# yaw.net
KiCad netlist of a schematic drawn in EAGLE
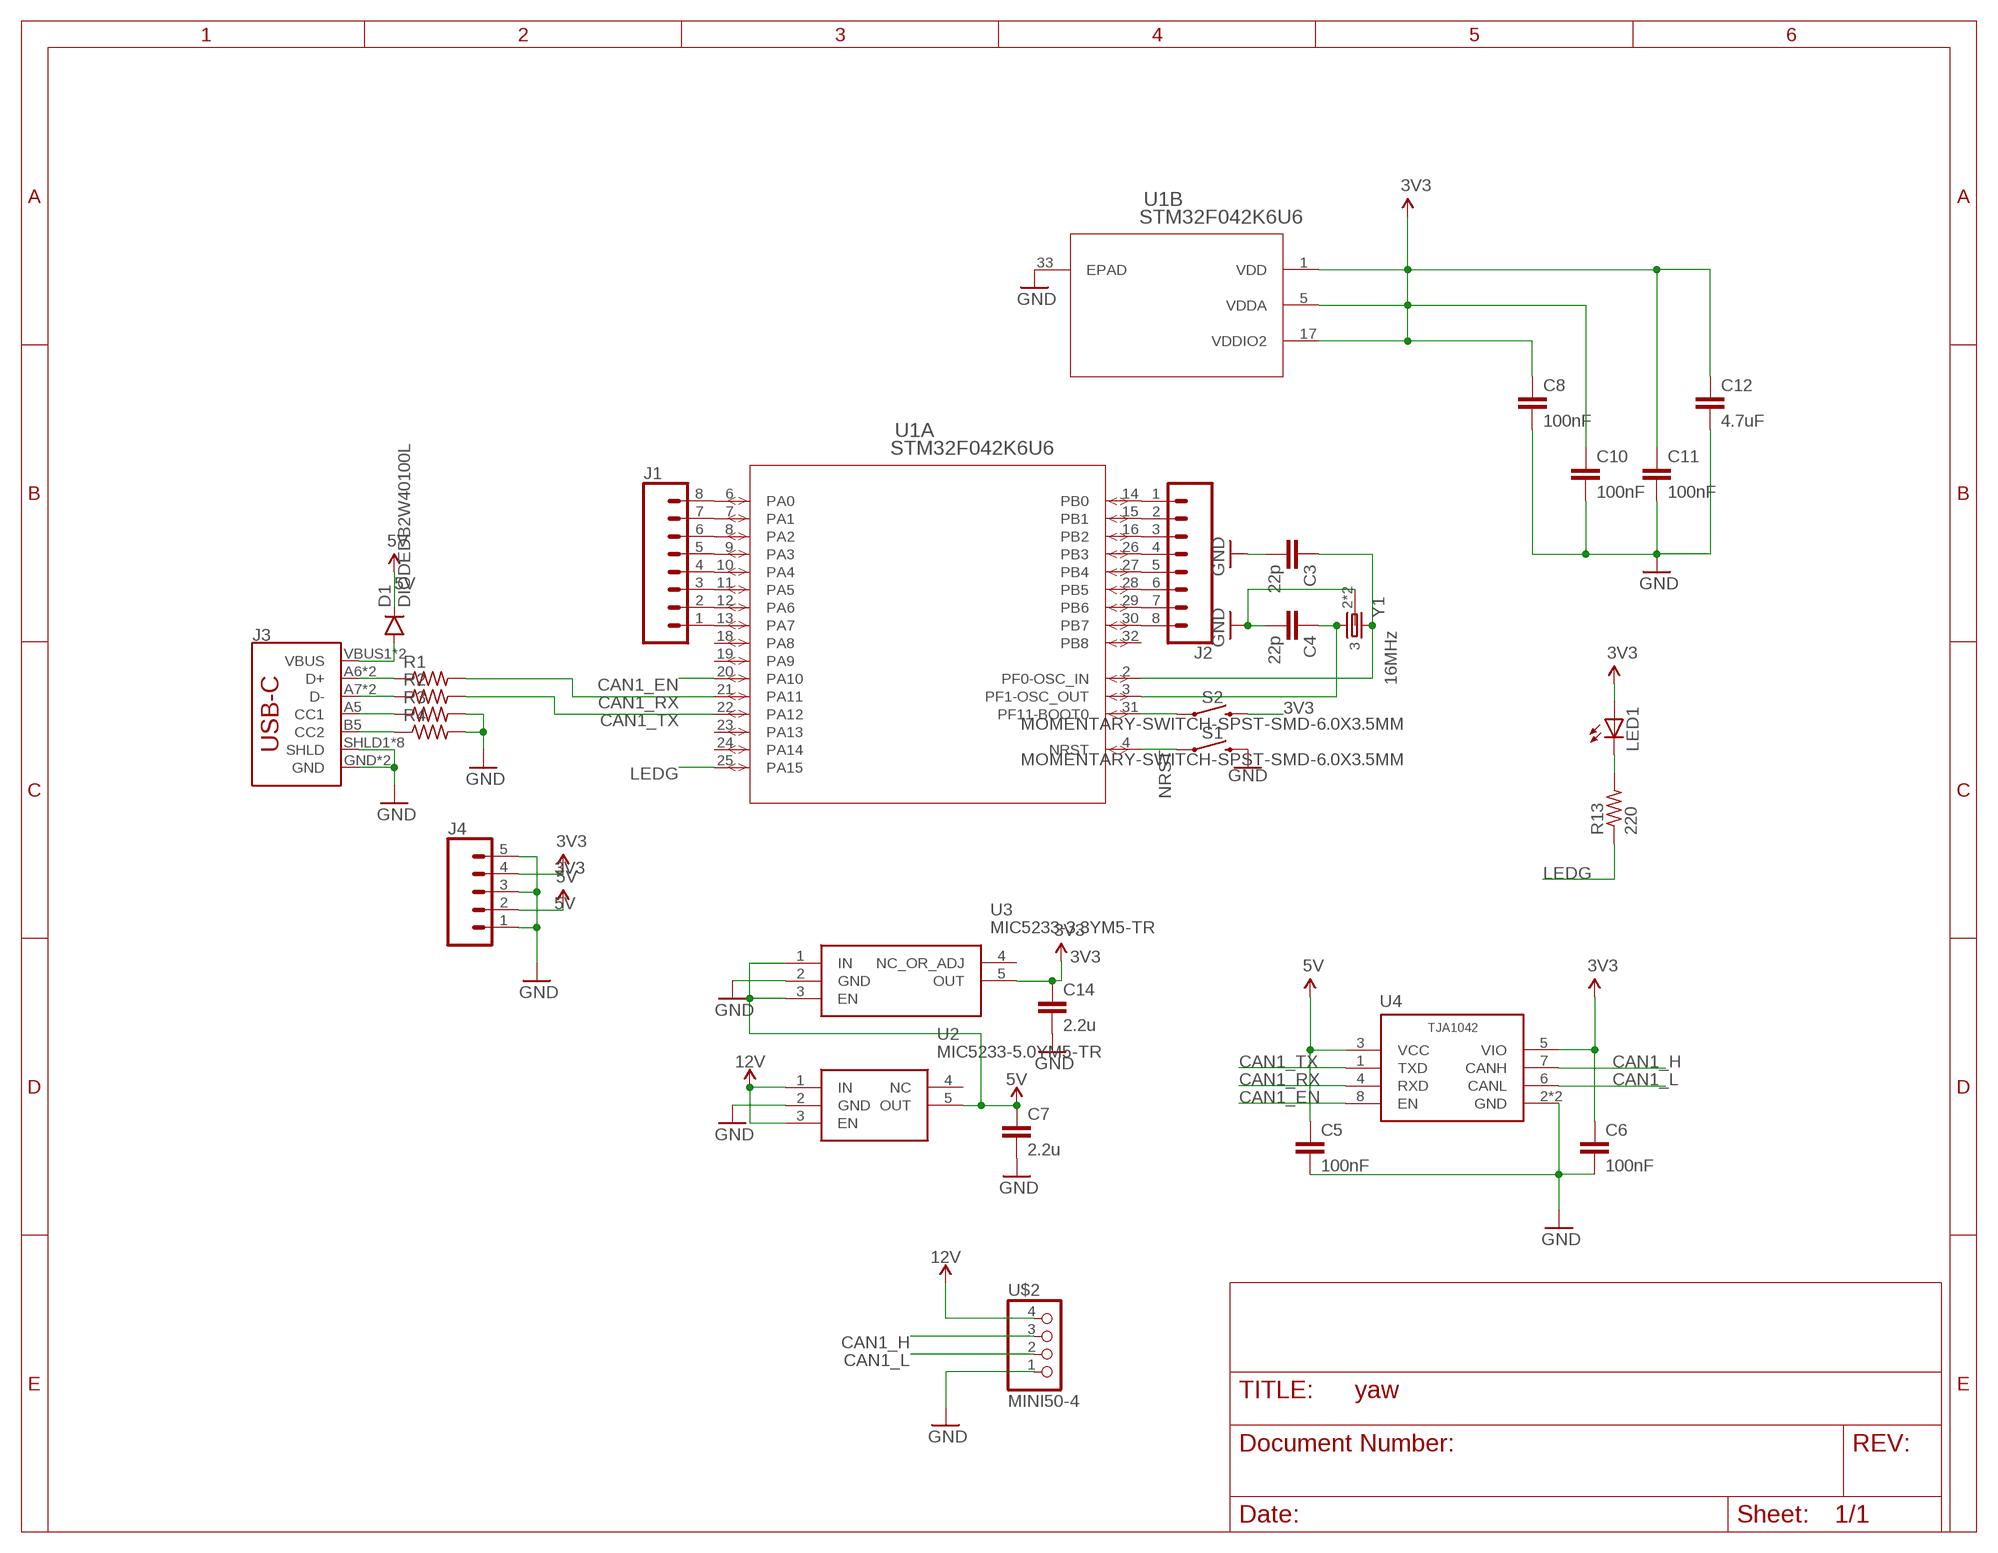
[diagram p0: schematic, sheet 1]

(export (version "E")
  (design (tool "Eeschema 10.0.6"))
  (components
    (comp (ref "C3")
      (value "22p")
      (footprint "eagle-import:0603-C")
      (libsource (lib "eagle-import") (part "C0603"))
    )
    (comp (ref "C4")
      (value "22p")
      (footprint "eagle-import:0603-C")
      (libsource (lib "eagle-import") (part "C0603"))
    )
    (comp (ref "C5")
      (value "100nF")
      (footprint "eagle-import:0603-C")
      (libsource (lib "eagle-import") (part "C0603"))
    )
    (comp (ref "C6")
      (value "100nF")
      (footprint "eagle-import:0603-C")
      (libsource (lib "eagle-import") (part "C0603"))
    )
    (comp (ref "C7")
      (value "2.2u")
      (footprint "eagle-import:C0603")
      (libsource (lib "eagle-import") (part "C-EUC0603"))
    )
    (comp (ref "C8")
      (value "100nF")
      (footprint "eagle-import:0603-C")
      (libsource (lib "eagle-import") (part "C0603"))
    )
    (comp (ref "C10")
      (value "100nF")
      (footprint "eagle-import:0603-C")
      (libsource (lib "eagle-import") (part "C0603"))
    )
    (comp (ref "C11")
      (value "100nF")
      (footprint "eagle-import:0603-C")
      (libsource (lib "eagle-import") (part "C0603"))
    )
    (comp (ref "C12")
      (value "4.7uF")
      (footprint "eagle-import:0603-C")
      (libsource (lib "eagle-import") (part "C0603"))
    )
    (comp (ref "C14")
      (value "2.2u")
      (footprint "eagle-import:C0603")
      (libsource (lib "eagle-import") (part "C-EUC0603"))
    )
    (comp (ref "D1")
      (value "DIODEDB2W40100L")
      (footprint "eagle-import:SOD-123F")
      (libsource (lib "eagle-import") (part "DIODEDB2W40100L"))
    )
    (comp (ref "J1")
      (value "CONN_08\"")
      (footprint "eagle-import:1X08")
      (libsource (lib "eagle-import") (part "CONN_08{dblquote}"))
    )
    (comp (ref "J2")
      (value "CONN_08\"")
      (footprint "eagle-import:1X08")
      (libsource (lib "eagle-import") (part "CONN_08{dblquote}"))
    )
    (comp (ref "J3")
      (value "USB-C-BREAKOUT_SPARKFUN-CONNECTORS_USB_C16PIN")
      (footprint "eagle-import:USB-C-BREAKOUT_SPARKFUN-CONNECTORS_USB-C-16P")
      (libsource (lib "eagle-import") (part "USB-C-BREAKOUT_SPARKFUN-CONNECTORS_USB_C16PIN"))
    )
    (comp (ref "J4")
      (value "CONN_05")
      (footprint "eagle-import:1X05")
      (libsource (lib "eagle-import") (part "CONN_05"))
    )
    (comp (ref "LED1")
      (value "LEDCHIPLED_0805")
      (footprint "eagle-import:CHIPLED_0805")
      (libsource (lib "eagle-import") (part "LEDCHIPLED_0805"))
    )
    (comp (ref "R1")
      (value "R0402")
      (footprint "eagle-import:0402-R")
      (libsource (lib "eagle-import") (part "R0402"))
    )
    (comp (ref "R2")
      (value "R0402")
      (footprint "eagle-import:0402-R")
      (libsource (lib "eagle-import") (part "R0402"))
    )
    (comp (ref "R3")
      (value "R0402")
      (footprint "eagle-import:0402-R")
      (libsource (lib "eagle-import") (part "R0402"))
    )
    (comp (ref "R4")
      (value "R0402")
      (footprint "eagle-import:0402-R")
      (libsource (lib "eagle-import") (part "R0402"))
    )
    (comp (ref "R13")
      (value "220")
      (footprint "eagle-import:0402-R")
      (libsource (lib "eagle-import") (part "R0402"))
    )
    (comp (ref "S1")
      (value "MOMENTARY-SWITCH-SPST-SMD-6.0X3.5MM")
      (footprint "eagle-import:TACTILE_SWITCH_SMD_6.0X3.5MM")
      (libsource (lib "eagle-import") (part "MOMENTARY-SWITCH-SPST-SMD-6.0X3.5MM"))
    )
    (comp (ref "S2")
      (value "MOMENTARY-SWITCH-SPST-SMD-6.0X3.5MM")
      (footprint "eagle-import:TACTILE_SWITCH_SMD_6.0X3.5MM")
      (libsource (lib "eagle-import") (part "MOMENTARY-SWITCH-SPST-SMD-6.0X3.5MM"))
    )
    (comp (ref "U$2")
      (value "MINI50-4")
      (footprint "eagle-import:MINI50")
      (libsource (lib "eagle-import") (part "MINI50-4"))
    )
    (comp (ref "U1")
      (value "STM32F042K6U6")
      (footprint "eagle-import:UFQFPN32-5X5MM")
      (fields (field (name "COPYRIGHT") "Copyright (C) 2018 Accelerated Designs. All rights reserved"))
      (libsource (lib "eagle-import") (part "STM32F042K6U6"))
    )
    (comp (ref "U2")
      (value "MIC5233-5.0YM5-TR")
      (footprint "eagle-import:SOT95P280X145-5N")
      (fields (field (name "MOUSER_PART_NUMBER") "998-MIC5233-5.0YM5TR"))
      (libsource (lib "eagle-import") (part "MIC5233-5.0YM5-TR"))
    )
    (comp (ref "U3")
      (value "MIC5233-3.3YM5-TR")
      (footprint "eagle-import:SOT95P280X145-5N")
      (fields (field (name "MOUSER_PART_NUMBER") "998-MIC5233-3.3YM5TR"))
      (libsource (lib "eagle-import") (part "MIC5233-3.3YM5-TR"))
    )
    (comp (ref "U4")
      (value "TJA1042HVSON")
      (footprint "eagle-import:HVSON8")
      (libsource (lib "eagle-import") (part "TJA1042HVSON"))
    )
    (comp (ref "Y1")
      (value "16MHz")
      (footprint "eagle-import:XTAL-3.2X2.5")
      (libsource (lib "eagle-import") (part "CRYSTAL-3.2X2.54-PIN"))
    )
  )
  (nets
    (net (code "1") (name "/CAN1_EN") (class "Default")
      (node (ref "U1") (pin "20") (pinfunction "PA10_20") (pintype "bidirectional"))
      (node (ref "U4") (pin "8") (pinfunction "EN_8") (pintype "bidirectional"))
    )
    (net (code "2") (name "/CAN1_H") (class "Default")
      (node (ref "U$2") (pin "3") (pinfunction "2_3") (pintype "passive"))
      (node (ref "U4") (pin "7") (pinfunction "CANH_7") (pintype "bidirectional"))
    )
    (net (code "3") (name "/CAN1_L") (class "Default")
      (node (ref "U$2") (pin "2") (pinfunction "3_2") (pintype "passive"))
      (node (ref "U4") (pin "6") (pinfunction "CANL_6") (pintype "bidirectional"))
    )
    (net (code "4") (name "/CAN1_RX") (class "Default")
      (node (ref "R1") (pin "2") (pinfunction "2_2") (pintype "passive"))
      (node (ref "U1") (pin "21") (pinfunction "PA11_21") (pintype "bidirectional"))
      (node (ref "U4") (pin "4") (pinfunction "RXD_4") (pintype "bidirectional"))
    )
    (net (code "5") (name "/CAN1_TX") (class "Default")
      (node (ref "R2") (pin "2") (pinfunction "2_2") (pintype "passive"))
      (node (ref "U1") (pin "22") (pinfunction "PA12_22") (pintype "bidirectional"))
      (node (ref "U4") (pin "1") (pinfunction "TXD_1") (pintype "bidirectional"))
    )
    (net (code "6") (name "/LEDG") (class "Default")
      (node (ref "R13") (pin "1") (pinfunction "1_1") (pintype "passive"))
      (node (ref "U1") (pin "25") (pinfunction "PA15_25") (pintype "bidirectional"))
    )
    (net (code "7") (name "/NRST") (class "Default")
      (node (ref "S1") (pin "1") (pinfunction "1_1") (pintype "passive"))
      (node (ref "U1") (pin "4") (pinfunction "NRST_4") (pintype "bidirectional"))
    )
    (net (code "8") (name "3V3") (class "Default")
      (node (ref "C10") (pin "1") (pinfunction "1_1") (pintype "passive"))
      (node (ref "C11") (pin "1") (pinfunction "1_1") (pintype "passive"))
      (node (ref "C12") (pin "1") (pinfunction "1_1") (pintype "passive"))
      (node (ref "C14") (pin "1") (pinfunction "1_1") (pintype "passive"))
      (node (ref "C6") (pin "1") (pinfunction "1_1") (pintype "passive"))
      (node (ref "C8") (pin "1") (pinfunction "1_1") (pintype "passive"))
      (node (ref "J4") (pin "4") (pinfunction "4_4") (pintype "passive"))
      (node (ref "LED1") (pin "A") (pinfunction "A_A") (pintype "passive"))
      (node (ref "S2") (pin "2") (pinfunction "2_2") (pintype "passive"))
      (node (ref "U1") (pin "1") (pinfunction "VDD_1") (pintype "power_in"))
      (node (ref "U1") (pin "17") (pinfunction "VDDIO2_17") (pintype "power_in"))
      (node (ref "U1") (pin "5") (pinfunction "VDDA_5") (pintype "power_in"))
      (node (ref "U3") (pin "5") (pinfunction "OUT_5") (pintype "bidirectional"))
      (node (ref "U4") (pin "5") (pinfunction "VIO_5") (pintype "bidirectional"))
    )
    (net (code "9") (name "5V") (class "Default")
      (node (ref "C5") (pin "1") (pinfunction "1_1") (pintype "passive"))
      (node (ref "C7") (pin "1") (pinfunction "1_1") (pintype "passive"))
      (node (ref "D1") (pin "1") (pinfunction "C_1") (pintype "passive"))
      (node (ref "J4") (pin "2") (pinfunction "2_2") (pintype "passive"))
      (node (ref "U2") (pin "5") (pinfunction "OUT_5") (pintype "bidirectional"))
      (node (ref "U3") (pin "1") (pinfunction "IN_1") (pintype "bidirectional"))
      (node (ref "U3") (pin "3") (pinfunction "EN_3") (pintype "bidirectional"))
      (node (ref "U4") (pin "3") (pinfunction "VCC_3") (pintype "bidirectional"))
    )
    (net (code "10") (name "12V") (class "Default")
      (node (ref "U$2") (pin "4") (pinfunction "1_4") (pintype "passive"))
      (node (ref "U2") (pin "1") (pinfunction "IN_1") (pintype "bidirectional"))
      (node (ref "U2") (pin "3") (pinfunction "EN_3") (pintype "bidirectional"))
    )
    (net (code "11") (name "GND") (class "Default")
      (node (ref "C10") (pin "2") (pinfunction "2_2") (pintype "passive"))
      (node (ref "C11") (pin "2") (pinfunction "2_2") (pintype "passive"))
      (node (ref "C12") (pin "2") (pinfunction "2_2") (pintype "passive"))
      (node (ref "C14") (pin "2") (pinfunction "2_2") (pintype "passive"))
      (node (ref "C3") (pin "2") (pinfunction "2_2") (pintype "passive"))
      (node (ref "C4") (pin "2") (pinfunction "2_2") (pintype "passive"))
      (node (ref "C5") (pin "2") (pinfunction "2_2") (pintype "passive"))
      (node (ref "C6") (pin "2") (pinfunction "2_2") (pintype "passive"))
      (node (ref "C7") (pin "2") (pinfunction "2_2") (pintype "passive"))
      (node (ref "C8") (pin "2") (pinfunction "2_2") (pintype "passive"))
      (node (ref "J3") (pin "GND") (pinfunction "GND_GND") (pintype "bidirectional"))
      (node (ref "J3") (pin "GND2") (pinfunction "GND_GND2") (pintype "bidirectional"))
      (node (ref "J3") (pin "SHLD1") (pinfunction "SHLD_SHLD1") (pintype "bidirectional"))
      (node (ref "J3") (pin "SHLD2") (pinfunction "SHLD_SHLD2") (pintype "bidirectional"))
      (node (ref "J3") (pin "SHLD3") (pinfunction "SHLD_SHLD3") (pintype "bidirectional"))
      (node (ref "J3") (pin "SHLD4") (pinfunction "SHLD_SHLD4") (pintype "bidirectional"))
      (node (ref "J3") (pin "SHLD5") (pinfunction "SHLD_SHLD5") (pintype "bidirectional"))
      (node (ref "J3") (pin "SHLD6") (pinfunction "SHLD_SHLD6") (pintype "bidirectional"))
      (node (ref "J3") (pin "SHLD7") (pinfunction "SHLD_SHLD7") (pintype "bidirectional"))
      (node (ref "J3") (pin "SHLD8") (pinfunction "SHLD_SHLD8") (pintype "bidirectional"))
      (node (ref "J4") (pin "1") (pinfunction "1_1") (pintype "passive"))
      (node (ref "J4") (pin "3") (pinfunction "3_3") (pintype "passive"))
      (node (ref "J4") (pin "5") (pinfunction "5_5") (pintype "passive"))
      (node (ref "R3") (pin "2") (pinfunction "2_2") (pintype "passive"))
      (node (ref "R4") (pin "2") (pinfunction "2_2") (pintype "passive"))
      (node (ref "S1") (pin "2") (pinfunction "2_2") (pintype "passive"))
      (node (ref "U$2") (pin "1") (pinfunction "4_1") (pintype "passive"))
      (node (ref "U1") (pin "33") (pinfunction "EPAD_33") (pintype "passive"))
      (node (ref "U2") (pin "2") (pinfunction "GND_2") (pintype "bidirectional"))
      (node (ref "U3") (pin "2") (pinfunction "GND_2") (pintype "bidirectional"))
      (node (ref "U4") (pin "2") (pinfunction "GND_2") (pintype "bidirectional"))
      (node (ref "U4") (pin "PAD") (pinfunction "GND_PAD") (pintype "bidirectional"))
      (node (ref "Y1") (pin "2") (pinfunction "3_2") (pintype "bidirectional"))
      (node (ref "Y1") (pin "4") (pinfunction "3_4") (pintype "bidirectional"))
    )
    (net (code "12") (name "Net-(D1-A)") (class "Default")
      (node (ref "D1") (pin "2") (pinfunction "A_2") (pintype "passive"))
      (node (ref "J3") (pin "VBUS1") (pinfunction "VBUS_VBUS1") (pintype "bidirectional"))
      (node (ref "J3") (pin "VBUS2") (pinfunction "VBUS_VBUS2") (pintype "bidirectional"))
    )
    (net (code "13") (name "Net-(J3-CC1)") (class "Default")
      (node (ref "J3") (pin "A5") (pinfunction "CC1_A5") (pintype "bidirectional"))
      (node (ref "R3") (pin "1") (pinfunction "1_1") (pintype "passive"))
    )
    (net (code "14") (name "Net-(J3-CC2)") (class "Default")
      (node (ref "J3") (pin "B5") (pinfunction "CC2_B5") (pintype "bidirectional"))
      (node (ref "R4") (pin "1") (pinfunction "1_1") (pintype "passive"))
    )
    (net (code "15") (name "Net-(J3-D+-PadA6)") (class "Default")
      (node (ref "J3") (pin "A6") (pinfunction "D+_A6") (pintype "bidirectional"))
      (node (ref "J3") (pin "B6") (pinfunction "D+_B6") (pintype "bidirectional"))
      (node (ref "R1") (pin "1") (pinfunction "1_1") (pintype "passive"))
    )
    (net (code "16") (name "Net-(J3-D--PadA7)") (class "Default")
      (node (ref "J3") (pin "A7") (pinfunction "D-_A7") (pintype "bidirectional"))
      (node (ref "J3") (pin "B7") (pinfunction "D-_B7") (pintype "bidirectional"))
      (node (ref "R2") (pin "1") (pinfunction "1_1") (pintype "passive"))
    )
    (net (code "17") (name "Net-(LED1-PadC)") (class "Default")
      (node (ref "LED1") (pin "C") (pinfunction "C_C") (pintype "passive"))
      (node (ref "R13") (pin "2") (pinfunction "2_2") (pintype "passive"))
    )
    (net (code "18") (name "Net-(U1A-PA0)") (class "Default")
      (node (ref "J1") (pin "8") (pinfunction "8_8") (pintype "passive"))
      (node (ref "U1") (pin "6") (pinfunction "PA0_6") (pintype "bidirectional"))
    )
    (net (code "19") (name "Net-(U1A-PA1)") (class "Default")
      (node (ref "J1") (pin "7") (pinfunction "7_7") (pintype "passive"))
      (node (ref "U1") (pin "7") (pinfunction "PA1_7") (pintype "bidirectional"))
    )
    (net (code "20") (name "Net-(U1A-PA2)") (class "Default")
      (node (ref "J1") (pin "6") (pinfunction "6_6") (pintype "passive"))
      (node (ref "U1") (pin "8") (pinfunction "PA2_8") (pintype "bidirectional"))
    )
    (net (code "21") (name "Net-(U1A-PA3)") (class "Default")
      (node (ref "J1") (pin "5") (pinfunction "5_5") (pintype "passive"))
      (node (ref "U1") (pin "9") (pinfunction "PA3_9") (pintype "bidirectional"))
    )
    (net (code "22") (name "Net-(U1A-PA4)") (class "Default")
      (node (ref "J1") (pin "4") (pinfunction "4_4") (pintype "passive"))
      (node (ref "U1") (pin "10") (pinfunction "PA4_10") (pintype "bidirectional"))
    )
    (net (code "23") (name "Net-(U1A-PA5)") (class "Default")
      (node (ref "J1") (pin "3") (pinfunction "3_3") (pintype "passive"))
      (node (ref "U1") (pin "11") (pinfunction "PA5_11") (pintype "bidirectional"))
    )
    (net (code "24") (name "Net-(U1A-PA6)") (class "Default")
      (node (ref "J1") (pin "2") (pinfunction "2_2") (pintype "passive"))
      (node (ref "U1") (pin "12") (pinfunction "PA6_12") (pintype "bidirectional"))
    )
    (net (code "25") (name "Net-(U1A-PA7)") (class "Default")
      (node (ref "J1") (pin "1") (pinfunction "1_1") (pintype "passive"))
      (node (ref "U1") (pin "13") (pinfunction "PA7_13") (pintype "bidirectional"))
    )
    (net (code "26") (name "Net-(U1A-PB0)") (class "Default")
      (node (ref "J2") (pin "1") (pinfunction "1_1") (pintype "passive"))
      (node (ref "U1") (pin "14") (pinfunction "PB0_14") (pintype "bidirectional"))
    )
    (net (code "27") (name "Net-(U1A-PB1)") (class "Default")
      (node (ref "J2") (pin "2") (pinfunction "2_2") (pintype "passive"))
      (node (ref "U1") (pin "15") (pinfunction "PB1_15") (pintype "bidirectional"))
    )
    (net (code "28") (name "Net-(U1A-PB2)") (class "Default")
      (node (ref "J2") (pin "3") (pinfunction "3_3") (pintype "passive"))
      (node (ref "U1") (pin "16") (pinfunction "PB2_16") (pintype "bidirectional"))
    )
    (net (code "29") (name "Net-(U1A-PB3)") (class "Default")
      (node (ref "J2") (pin "4") (pinfunction "4_4") (pintype "passive"))
      (node (ref "U1") (pin "26") (pinfunction "PB3_26") (pintype "bidirectional"))
    )
    (net (code "30") (name "Net-(U1A-PB4)") (class "Default")
      (node (ref "J2") (pin "5") (pinfunction "5_5") (pintype "passive"))
      (node (ref "U1") (pin "27") (pinfunction "PB4_27") (pintype "bidirectional"))
    )
    (net (code "31") (name "Net-(U1A-PB5)") (class "Default")
      (node (ref "J2") (pin "6") (pinfunction "6_6") (pintype "passive"))
      (node (ref "U1") (pin "28") (pinfunction "PB5_28") (pintype "bidirectional"))
    )
    (net (code "32") (name "Net-(U1A-PB6)") (class "Default")
      (node (ref "J2") (pin "7") (pinfunction "7_7") (pintype "passive"))
      (node (ref "U1") (pin "29") (pinfunction "PB6_29") (pintype "bidirectional"))
    )
    (net (code "33") (name "Net-(U1A-PB7)") (class "Default")
      (node (ref "J2") (pin "8") (pinfunction "8_8") (pintype "passive"))
      (node (ref "U1") (pin "30") (pinfunction "PB7_30") (pintype "bidirectional"))
    )
    (net (code "34") (name "Net-(U1A-PF0-OSC_IN)") (class "Default")
      (node (ref "C3") (pin "1") (pinfunction "1_1") (pintype "passive"))
      (node (ref "U1") (pin "2") (pinfunction "PF0-OSC_IN_2") (pintype "bidirectional"))
      (node (ref "Y1") (pin "1") (pinfunction "1_1") (pintype "passive"))
    )
    (net (code "35") (name "Net-(U1A-PF1-OSC_OUT)") (class "Default")
      (node (ref "C4") (pin "1") (pinfunction "1_1") (pintype "passive"))
      (node (ref "U1") (pin "3") (pinfunction "PF1-OSC_OUT_3") (pintype "bidirectional"))
      (node (ref "Y1") (pin "3") (pinfunction "2_3") (pintype "passive"))
    )
    (net (code "36") (name "Net-(U1A-PF11-BOOT0)") (class "Default")
      (node (ref "S2") (pin "1") (pinfunction "1_1") (pintype "passive"))
      (node (ref "U1") (pin "31") (pinfunction "PF11-BOOT0_31") (pintype "bidirectional"))
    )
    (net (code "37") (name "unconnected-(U1A-PA8-Pad18)") (class "Default")
      (node (ref "U1") (pin "18") (pinfunction "PA8_18") (pintype "bidirectional"))
    )
    (net (code "38") (name "unconnected-(U1A-PA9-Pad19)") (class "Default")
      (node (ref "U1") (pin "19") (pinfunction "PA9_19") (pintype "bidirectional"))
    )
    (net (code "39") (name "unconnected-(U1A-PA13-Pad23)") (class "Default")
      (node (ref "U1") (pin "23") (pinfunction "PA13_23") (pintype "bidirectional"))
    )
    (net (code "40") (name "unconnected-(U1A-PA14-Pad24)") (class "Default")
      (node (ref "U1") (pin "24") (pinfunction "PA14_24") (pintype "bidirectional"))
    )
    (net (code "41") (name "unconnected-(U1A-PB8-Pad32)") (class "Default")
      (node (ref "U1") (pin "32") (pinfunction "PB8_32") (pintype "bidirectional"))
    )
    (net (code "42") (name "unconnected-(U2-NC-Pad4)") (class "Default")
      (node (ref "U2") (pin "4") (pinfunction "NC_4") (pintype "no_connect"))
    )
    (net (code "43") (name "unconnected-(U3-NC_OR_ADJ-Pad4)") (class "Default")
      (node (ref "U3") (pin "4") (pinfunction "NC_OR_ADJ_4") (pintype "bidirectional"))
    )
  )
)
